# RS485.net
KiCad netlist of a schematic drawn in Altium Designer
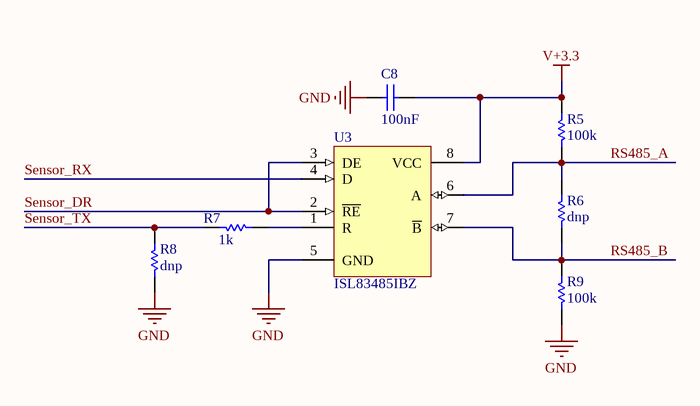
[diagram p0: RS485.SchDoc]

(export (version "E")
  (design (tool "Eeschema 10.0.6"))
  (components
    (comp (ref "C8")
      (value "100nF")
      (footprint "0603")
      (description "Capacitor (Semiconductor SIM Model)")
      (fields (field (name "PUBLISHER") "Altium Limited"))
      (libsource (lib "Miscellaneous Devices") (part "Cap Semi"))
    )
    (comp (ref "R5")
      (value "100k")
      (footprint "0603")
      (description "Semiconductor Resistor")
      (fields (field (name "PUBLISHER") "Altium Limited"))
      (libsource (lib "Miscellaneous Devices") (part "Res Semi"))
    )
    (comp (ref "R6")
      (value "dnp")
      (footprint "0603")
      (description "Semiconductor Resistor")
      (fields (field (name "PUBLISHER") "Altium Limited"))
      (libsource (lib "Miscellaneous Devices") (part "Res Semi"))
    )
    (comp (ref "R7")
      (value "1k")
      (footprint "0603")
      (description "Semiconductor Resistor")
      (fields (field (name "PUBLISHER") "Altium Limited"))
      (libsource (lib "") (part "Res Semi_1"))
    )
    (comp (ref "R8")
      (value "dnp")
      (footprint "0603")
      (description "Semiconductor Resistor")
      (fields (field (name "PUBLISHER") "Altium Limited"))
      (libsource (lib "") (part "Res Semi_1"))
    )
    (comp (ref "R9")
      (value "100k")
      (footprint "0603")
      (description "Semiconductor Resistor")
      (fields (field (name "PUBLISHER") "Altium Limited"))
      (libsource (lib "Miscellaneous Devices") (part "Res Semi"))
    )
    (comp (ref "U3")
      (value "ISL83485IBZ")
      (footprint "SO8")
      (description "Differential Bus Transceiver")
      (fields (field (name "PUBLISHER") "Altium Limited"))
      (libsource (lib "wireless server") (part "SN75176AD"))
    )
  )
  (nets
    (net (code "1") (name "/RS485_A") (class "Default")
      (node (ref "R5") (pin "2") (pinfunction "2_2") (pintype "passive"))
      (node (ref "R6") (pin "1") (pinfunction "1_1") (pintype "passive"))
      (node (ref "U3") (pin "6") (pinfunction "A_6") (pintype "bidirectional"))
    )
    (net (code "2") (name "/RS485_B") (class "Default")
      (node (ref "R6") (pin "2") (pinfunction "2_2") (pintype "passive"))
      (node (ref "R9") (pin "1") (pinfunction "1_1") (pintype "passive"))
      (node (ref "U3") (pin "7") (pinfunction "~{B}_7") (pintype "bidirectional"))
    )
    (net (code "3") (name "/Sensor_DR") (class "Default")
      (node (ref "U3") (pin "2") (pinfunction "~{RE}_2") (pintype "input"))
      (node (ref "U3") (pin "3") (pinfunction "DE_3") (pintype "input"))
    )
    (net (code "4") (name "/Sensor_RX") (class "Default")
      (node (ref "U3") (pin "4") (pinfunction "D_4") (pintype "input"))
    )
    (net (code "5") (name "/Sensor_TX") (class "Default")
      (node (ref "R7") (pin "1") (pinfunction "1_1") (pintype "passive"))
      (node (ref "R8") (pin "2") (pinfunction "2_2") (pintype "passive"))
    )
    (net (code "6") (name "GND") (class "Default")
      (node (ref "C8") (pin "2") (pinfunction "2_2") (pintype "passive"))
      (node (ref "R8") (pin "1") (pinfunction "1_1") (pintype "passive"))
      (node (ref "R9") (pin "2") (pinfunction "2_2") (pintype "passive"))
      (node (ref "U3") (pin "5") (pinfunction "GND_5") (pintype "power_in"))
    )
    (net (code "7") (name "Net-(U3-R)") (class "Default")
      (node (ref "R7") (pin "2") (pinfunction "2_2") (pintype "passive"))
      (node (ref "U3") (pin "1") (pinfunction "R_1") (pintype "tri_state"))
    )
    (net (code "8") (name "V+3.3") (class "Default")
      (node (ref "C8") (pin "1") (pinfunction "1_1") (pintype "passive"))
      (node (ref "R5") (pin "1") (pinfunction "1_1") (pintype "passive"))
      (node (ref "U3") (pin "8") (pinfunction "VCC_8") (pintype "power_in"))
    )
  )
)
